# AudioCodec.net
KiCad netlist of a schematic drawn in Altium Designer
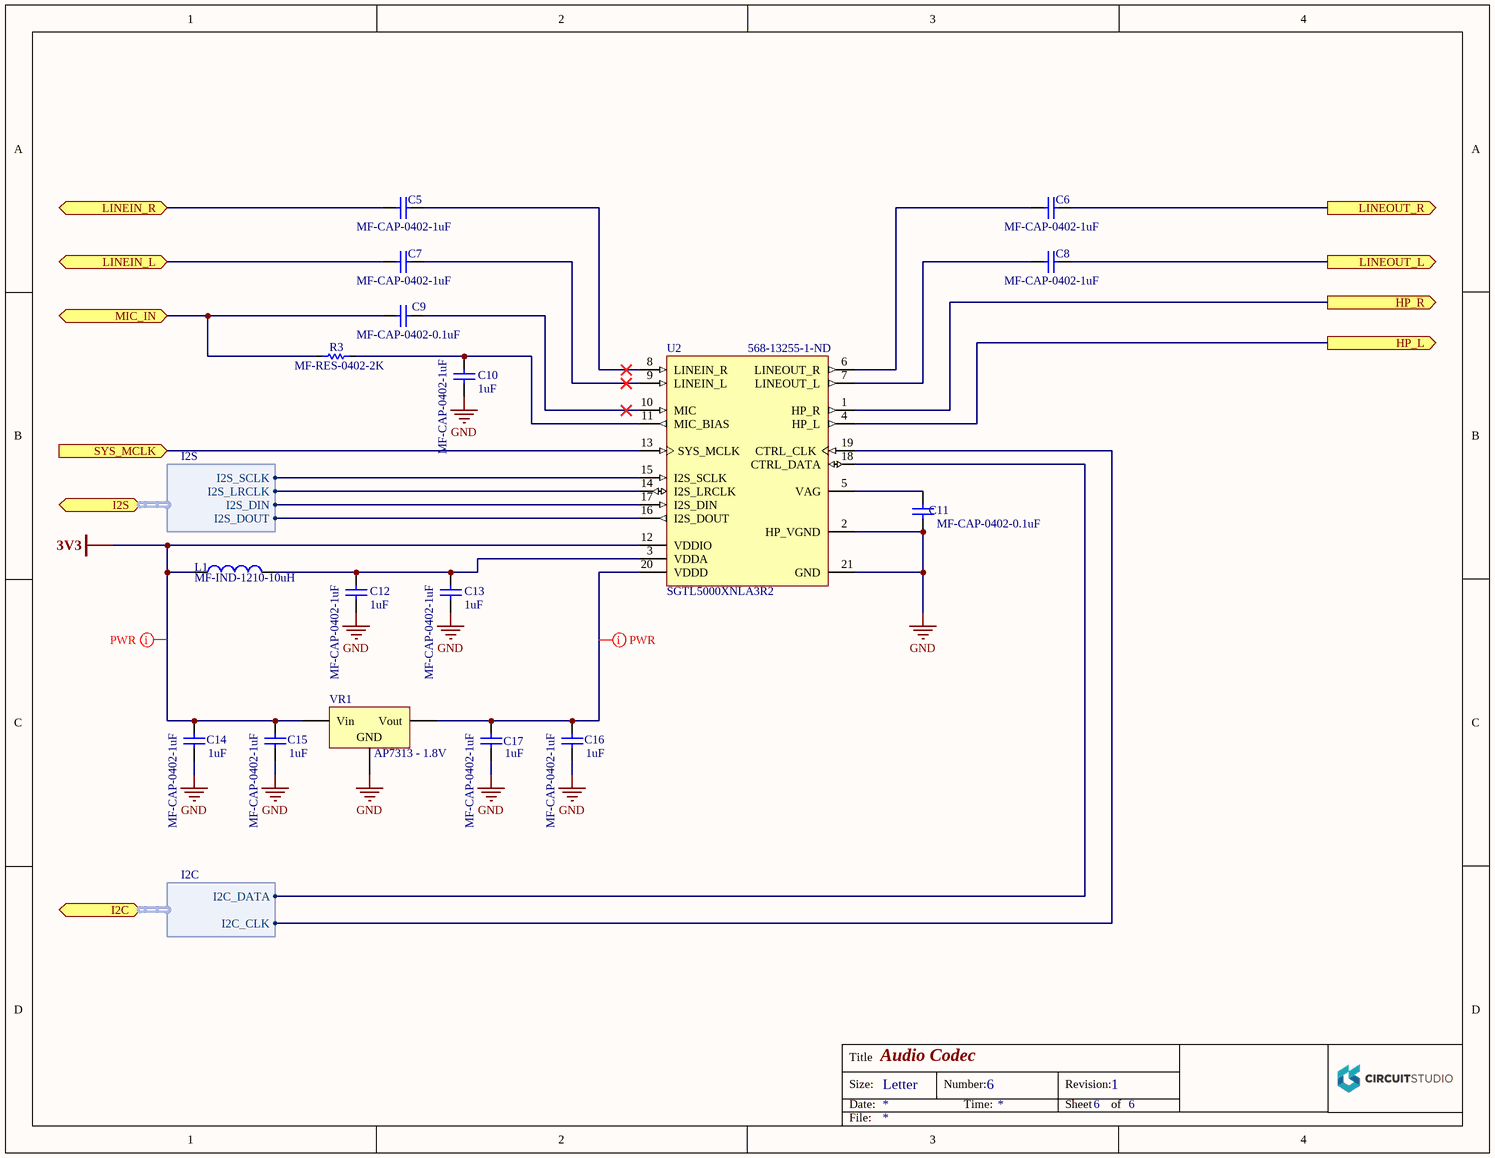
[diagram p0: AudioCodec.SchDoc]

(export (version "E")
  (design (tool "Eeschema 10.0.6"))
  (components
    (comp (ref "C5")
      (value "MF-CAP-0402-1uF")
      (footprint "C0402N")
      (fields
        (field (name "HOUSEPART") "YES")
        (field (name "TOLERANCE") "10%")
        (field (name "VOLTAGE") "16V")
      )
      (libsource (lib "MF_Passives") (part "CAPACITOR_NP"))
    )
    (comp (ref "C6")
      (value "MF-CAP-0402-1uF")
      (footprint "C0402N")
      (fields
        (field (name "HOUSEPART") "YES")
        (field (name "TOLERANCE") "10%")
        (field (name "VOLTAGE") "16V")
      )
      (libsource (lib "MF_Passives") (part "CAPACITOR_NP"))
    )
    (comp (ref "C7")
      (value "MF-CAP-0402-1uF")
      (footprint "C0402N")
      (fields
        (field (name "HOUSEPART") "YES")
        (field (name "TOLERANCE") "10%")
        (field (name "VOLTAGE") "16V")
      )
      (libsource (lib "MF_Passives") (part "CAPACITOR_NP"))
    )
    (comp (ref "C8")
      (value "MF-CAP-0402-1uF")
      (footprint "C0402N")
      (fields
        (field (name "HOUSEPART") "YES")
        (field (name "TOLERANCE") "10%")
        (field (name "VOLTAGE") "16V")
      )
      (libsource (lib "MF_Passives") (part "CAPACITOR_NP"))
    )
    (comp (ref "C9")
      (value "MF-CAP-0402-0.1uF")
      (footprint "C0402N")
      (fields
        (field (name "HOUSEPART") "YES")
        (field (name "TOLERANCE") "10%")
        (field (name "VOLTAGE") "16V")
      )
      (libsource (lib "MF_Passives") (part "CAPACITOR_NP"))
    )
    (comp (ref "C10")
      (value "MF-CAP-0402-1uF")
      (footprint "C0402N")
      (fields (field (name "HOUSEPART") "YES") (field (name "CAPACITANCE") "1uF"))
      (libsource (lib "MF_Passives") (part "CAPACITOR_NP"))
    )
    (comp (ref "C11")
      (value "MF-CAP-0402-0.1uF")
      (footprint "C0402N")
      (fields
        (field (name "HOUSEPART") "YES")
        (field (name "TOLERANCE") "10%")
        (field (name "VOLTAGE") "16V")
      )
      (libsource (lib "MF_Passives") (part "CAPACITOR_NP"))
    )
    (comp (ref "C12")
      (value "MF-CAP-0402-1uF")
      (footprint "C0402N")
      (fields (field (name "HOUSEPART") "YES") (field (name "CAPACITANCE") "1uF"))
      (libsource (lib "MF_Passives") (part "CAPACITOR_NP"))
    )
    (comp (ref "C13")
      (value "MF-CAP-0402-1uF")
      (footprint "C0402N")
      (fields (field (name "HOUSEPART") "YES") (field (name "CAPACITANCE") "1uF"))
      (libsource (lib "MF_Passives") (part "CAPACITOR_NP"))
    )
    (comp (ref "C14")
      (value "MF-CAP-0402-1uF")
      (footprint "C0402N")
      (fields (field (name "HOUSEPART") "YES") (field (name "CAPACITANCE") "1uF"))
      (libsource (lib "MF_Passives") (part "CAPACITOR_NP"))
    )
    (comp (ref "C15")
      (value "MF-CAP-0402-1uF")
      (footprint "C0402N")
      (fields (field (name "HOUSEPART") "YES") (field (name "CAPACITANCE") "1uF"))
      (libsource (lib "MF_Passives") (part "CAPACITOR_NP"))
    )
    (comp (ref "C16")
      (value "MF-CAP-0402-1uF")
      (footprint "C0402N")
      (fields (field (name "HOUSEPART") "YES") (field (name "CAPACITANCE") "1uF"))
      (libsource (lib "MF_Passives") (part "CAPACITOR_NP"))
    )
    (comp (ref "C17")
      (value "MF-CAP-0402-1uF")
      (footprint "C0402N")
      (fields (field (name "HOUSEPART") "YES") (field (name "CAPACITANCE") "1uF"))
      (libsource (lib "MF_Passives") (part "CAPACITOR_NP"))
    )
    (comp (ref "L1")
      (value "MF-IND-1210-10uH")
      (footprint "L1210_N")
      (fields (field (name "HOUSEPART") "YES"))
      (libsource (lib "MF_Passives") (part "INDUCTOR"))
    )
    (comp (ref "R3")
      (value "MF-RES-0402-2K")
      (footprint "R0402L")
      (fields (field (name "HOUSEPART") "YES") (field (name "VOLTAGE") "50 V"))
      (libsource (lib "MF_Passives") (part "RESISTOR"))
    )
    (comp (ref "U2")
      (value "SGTL5000XNLA3R2")
      (footprint "FRES-2032-01_L")
      (fields
        (field (name "MANUFACTURER") "Freescale Semiconductor")
        (field (name "SUPPLIER PART NUMBER 1") "568-13255-1-ND")
      )
      (libsource (lib "Altium Content Vault") (part "CMP-1078-00004-1"))
    )
    (comp (ref "VR1")
      (value "AP7313 - 1.8V")
      (footprint "AP7313_L")
      (description "Voltage Regulator")
      (libsource (lib "IC_Power") (part "Volt Reg"))
    )
  )
  (nets
    (net (code "3") (name "/HP_L") (class "Default")
      (node (ref "U2") (pin "4") (pinfunction "HP_L_4") (pintype "output"))
    )
    (net (code "4") (name "/HP_R") (class "Default")
      (node (ref "U2") (pin "1") (pinfunction "HP_R_1") (pintype "output"))
    )
    (net (code "5") (name "/I2C_CLK") (class "Default")
      (node (ref "U2") (pin "19") (pinfunction "CTRL_CLK_19") (pintype "input"))
    )
    (net (code "6") (name "/I2C_DATA") (class "Default")
      (node (ref "U2") (pin "18") (pinfunction "CTRL_DATA_18") (pintype "bidirectional"))
    )
    (net (code "7") (name "/I2S_DIN") (class "Default")
      (node (ref "U2") (pin "17") (pinfunction "I2S_DIN_17") (pintype "input"))
    )
    (net (code "8") (name "/I2S_DOUT") (class "Default")
      (node (ref "U2") (pin "16") (pinfunction "I2S_DOUT_16") (pintype "output"))
    )
    (net (code "9") (name "/I2S_LRCLK") (class "Default")
      (node (ref "U2") (pin "14") (pinfunction "I2S_LRCLK_14") (pintype "bidirectional"))
    )
    (net (code "10") (name "/I2S_SCLK") (class "Default")
      (node (ref "U2") (pin "15") (pinfunction "I2S_SCLK_15") (pintype "input"))
    )
    (net (code "11") (name "/LINEIN_L") (class "Default")
      (node (ref "C7") (pin "2") (pinfunction "2_2") (pintype "passive"))
    )
    (net (code "12") (name "/LINEIN_R") (class "Default")
      (node (ref "C5") (pin "2") (pinfunction "2_2") (pintype "passive"))
    )
    (net (code "13") (name "/LINEOUT_L") (class "Default")
      (node (ref "C8") (pin "1") (pinfunction "1_1") (pintype "passive"))
    )
    (net (code "14") (name "/LINEOUT_R") (class "Default")
      (node (ref "C6") (pin "1") (pinfunction "1_1") (pintype "passive"))
    )
    (net (code "15") (name "/MIC_IN") (class "Default")
      (node (ref "C9") (pin "2") (pinfunction "2_2") (pintype "passive"))
      (node (ref "R3") (pin "1") (pinfunction "1_1") (pintype "passive"))
    )
    (net (code "16") (name "/SYS_MCLK") (class "Default")
      (node (ref "U2") (pin "13") (pinfunction "SYS_MCLK_13") (pintype "input"))
    )
    (net (code "19") (name "3V3") (class "Default")
      (node (ref "C14") (pin "1") (pinfunction "1_1") (pintype "passive"))
      (node (ref "C15") (pin "1") (pinfunction "1_1") (pintype "passive"))
      (node (ref "L1") (pin "1") (pinfunction "1_1") (pintype "passive"))
      (node (ref "U2") (pin "12") (pinfunction "VDDIO_12") (pintype "power_in"))
      (node (ref "VR1") (pin "1") (pinfunction "Vin_1") (pintype "passive"))
    )
    (net (code "20") (name "GND") (class "Default")
      (node (ref "C10") (pin "2") (pinfunction "2_2") (pintype "passive"))
      (node (ref "C11") (pin "2") (pinfunction "2_2") (pintype "passive"))
      (node (ref "C12") (pin "2") (pinfunction "2_2") (pintype "passive"))
      (node (ref "C13") (pin "2") (pinfunction "2_2") (pintype "passive"))
      (node (ref "C14") (pin "2") (pinfunction "2_2") (pintype "passive"))
      (node (ref "C15") (pin "2") (pinfunction "2_2") (pintype "passive"))
      (node (ref "C16") (pin "2") (pinfunction "2_2") (pintype "passive"))
      (node (ref "C17") (pin "2") (pinfunction "2_2") (pintype "passive"))
      (node (ref "U2") (pin "2") (pinfunction "HP_VGND_2") (pintype "power_in"))
      (node (ref "U2") (pin "21") (pinfunction "GND_21") (pintype "power_in"))
      (node (ref "VR1") (pin "3") (pinfunction "GND_3") (pintype "passive"))
    )
    (net (code "21") (name "Net-(U2-LINEIN_L)") (class "Default")
      (node (ref "C7") (pin "1") (pinfunction "1_1") (pintype "passive"))
      (node (ref "U2") (pin "9") (pinfunction "LINEIN_L_9") (pintype "input"))
    )
    (net (code "22") (name "Net-(U2-LINEIN_R)") (class "Default")
      (node (ref "C5") (pin "1") (pinfunction "1_1") (pintype "passive"))
      (node (ref "U2") (pin "8") (pinfunction "LINEIN_R_8") (pintype "input"))
    )
    (net (code "23") (name "Net-(U2-LINEOUT_L)") (class "Default")
      (node (ref "C8") (pin "2") (pinfunction "2_2") (pintype "passive"))
      (node (ref "U2") (pin "7") (pinfunction "LINEOUT_L_7") (pintype "output"))
    )
    (net (code "24") (name "Net-(U2-LINEOUT_R)") (class "Default")
      (node (ref "C6") (pin "2") (pinfunction "2_2") (pintype "passive"))
      (node (ref "U2") (pin "6") (pinfunction "LINEOUT_R_6") (pintype "output"))
    )
    (net (code "25") (name "Net-(U2-MIC)") (class "Default")
      (node (ref "C9") (pin "1") (pinfunction "1_1") (pintype "passive"))
      (node (ref "U2") (pin "10") (pinfunction "MIC_10") (pintype "input"))
    )
    (net (code "26") (name "Net-(U2-MIC_BIAS)") (class "Default")
      (node (ref "C10") (pin "1") (pinfunction "1_1") (pintype "passive"))
      (node (ref "R3") (pin "2") (pinfunction "2_2") (pintype "passive"))
      (node (ref "U2") (pin "11") (pinfunction "MIC_BIAS_11") (pintype "output"))
    )
    (net (code "27") (name "Net-(U2-VAG)") (class "Default")
      (node (ref "C11") (pin "1") (pinfunction "1_1") (pintype "passive"))
      (node (ref "U2") (pin "5") (pinfunction "VAG_5") (pintype "passive"))
    )
    (net (code "28") (name "Net-(U2-VDDA)") (class "Default")
      (node (ref "C12") (pin "1") (pinfunction "1_1") (pintype "passive"))
      (node (ref "C13") (pin "1") (pinfunction "1_1") (pintype "passive"))
      (node (ref "L1") (pin "2") (pinfunction "2_2") (pintype "passive"))
      (node (ref "U2") (pin "3") (pinfunction "VDDA_3") (pintype "power_in"))
    )
    (net (code "29") (name "Net-(U2-VDDD)") (class "Default")
      (node (ref "C16") (pin "1") (pinfunction "1_1") (pintype "passive"))
      (node (ref "C17") (pin "1") (pinfunction "1_1") (pintype "passive"))
      (node (ref "U2") (pin "20") (pinfunction "VDDD_20") (pintype "power_in"))
      (node (ref "VR1") (pin "2") (pinfunction "Vout_2") (pintype "passive"))
    )
  )
)
